# Power.net
KiCad netlist of a schematic drawn in Altium Designer
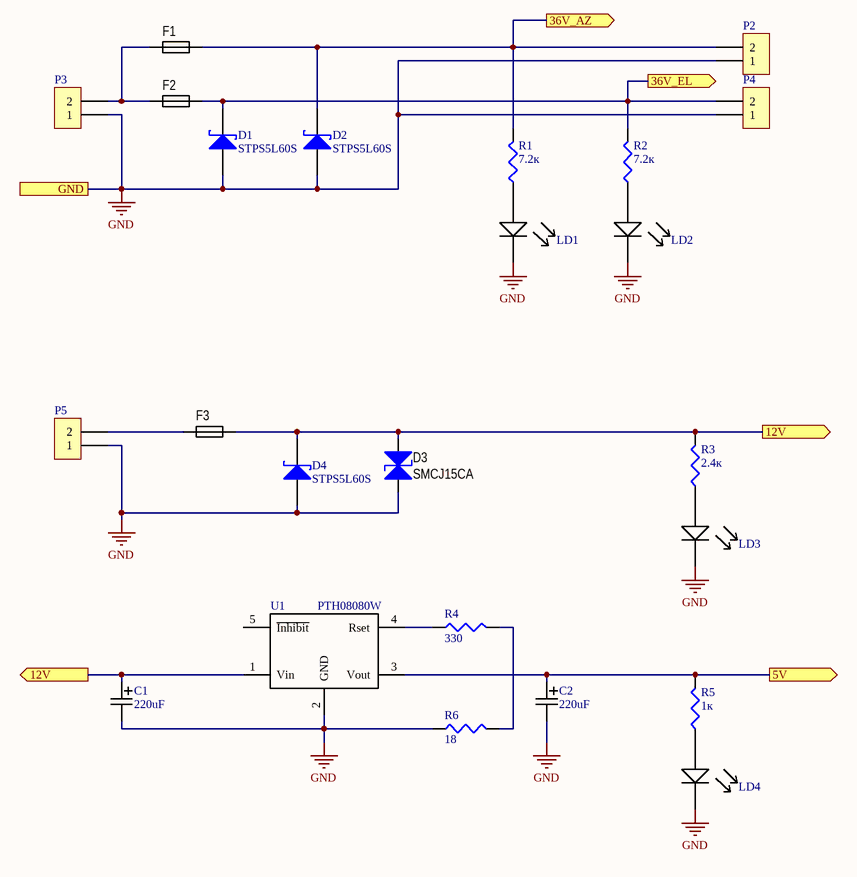
[diagram p0: Power.SchDoc]

(export (version "E")
  (design (tool "Eeschema 10.0.6"))
  (components
    (comp (ref "C1")
      (value "220uF")
      (footprint "ECAP SMD 8x10.5")
      (description "Конденсатор электролитический алюминиевый SMD 8x10.5мм")
      (libsource (lib "db") (part "ECAP SMD"))
    )
    (comp (ref "C2")
      (value "220uF")
      (footprint "ECAP SMD 8x10.5")
      (description "Конденсатор электролитический алюминиевый SMD 8x10.5мм")
      (libsource (lib "db") (part "ECAP SMD"))
    )
    (comp (ref "D1")
      (value "STPS5L60S")
      (footprint "SMCJ")
      (description "Диод Шоттки 60В 5А [SMC]")
      (libsource (lib "db") (part "STPS5L60S"))
    )
    (comp (ref "D2")
      (value "STPS5L60S")
      (footprint "SMCJ")
      (description "Диод Шоттки 60В 5А [SMC]")
      (libsource (lib "db") (part "STPS5L60S"))
    )
    (comp (ref "D3")
      (value "SMCJ15CA")
      (footprint "SMCJ_CA")
      (description "Супрессор двунаправленный")
      (libsource (lib "db") (part "SMCJ_CА"))
    )
    (comp (ref "D4")
      (value "STPS5L60S")
      (footprint "SMCJ")
      (description "Диод Шоттки 60В 5А [SMC]")
      (libsource (lib "db") (part "STPS5L60S"))
    )
    (comp (ref "F1")
      (value "FH-101C")
      (footprint "FH-101C")
      (description "Держатель предохранителя 5x20 с крышкой")
      (libsource (lib "db") (part "FH-101C"))
    )
    (comp (ref "F2")
      (value "FH-101C")
      (footprint "FH-101C")
      (description "Держатель предохранителя 5x20 с крышкой")
      (libsource (lib "db") (part "FH-101C"))
    )
    (comp (ref "F3")
      (value "FH-101C")
      (footprint "FH-101C")
      (description "Держатель предохранителя 5x20 с крышкой")
      (libsource (lib "db") (part "FH-101C"))
    )
    (comp (ref "LD1")
      (value "GNL-3012ED")
      (footprint "LED 3mm")
      (description "Светодиод красный 3мм")
      (libsource (lib "db") (part "GNL-3012ED"))
    )
    (comp (ref "LD2")
      (value "GNL-3012ED")
      (footprint "LED 3mm")
      (description "Светодиод красный 3мм")
      (libsource (lib "db") (part "GNL-3012ED"))
    )
    (comp (ref "LD3")
      (value "GNL-3012ED")
      (footprint "LED 3mm")
      (description "Светодиод красный 3мм")
      (libsource (lib "db") (part "GNL-3012ED"))
    )
    (comp (ref "LD4")
      (value "GNL-3012ED")
      (footprint "LED 3mm")
      (description "Светодиод красный 3мм")
      (libsource (lib "db") (part "GNL-3012ED"))
    )
    (comp (ref "P2")
      (value "2EDGR-5.0-02P")
      (footprint "2EDGR-5.0-02P")
      (description "Разъем штыревой на плату (папа)")
      (libsource (lib "db") (part "2EDGR-5.0-02P"))
    )
    (comp (ref "P3")
      (value "2EDGR-5.0-02P")
      (footprint "2EDGR-5.0-02P")
      (description "Разъем штыревой на плату (папа)")
      (libsource (lib "") (part "2EDGR-5.0-02P_1"))
    )
    (comp (ref "P4")
      (value "2EDGR-5.0-02P")
      (footprint "2EDGR-5.0-02P")
      (description "Разъем штыревой на плату (папа)")
      (libsource (lib "db") (part "2EDGR-5.0-02P"))
    )
    (comp (ref "P5")
      (value "15EDGRC-3.81-02")
      (footprint "15EDGRC-3.81-02")
      (description "Разъем штыревой на плату (папа)")
      (libsource (lib "db") (part "15EDGRC-3.81-02"))
    )
    (comp (ref "R1")
      (value "7.2к")
      (footprint "R1608-0603")
      (description "SMD резистор")
      (libsource (lib "db") (part "resistor"))
    )
    (comp (ref "R2")
      (value "7.2к")
      (footprint "R1608-0603")
      (description "SMD резистор")
      (libsource (lib "db") (part "resistor"))
    )
    (comp (ref "R3")
      (value "2.4к")
      (footprint "R1608-0603")
      (description "SMD резистор")
      (libsource (lib "db") (part "resistor"))
    )
    (comp (ref "R4")
      (value "330")
      (footprint "R1608-0603")
      (description "SMD резистор")
      (libsource (lib "db") (part "resistor"))
    )
    (comp (ref "R5")
      (value "1к")
      (footprint "R1608-0603")
      (description "SMD резистор")
      (libsource (lib "db") (part "resistor"))
    )
    (comp (ref "R6")
      (value "18")
      (footprint "R1608-0603")
      (description "SMD резистор")
      (libsource (lib "db") (part "resistor"))
    )
    (comp (ref "U1")
      (value "PTH08080W")
      (footprint "PTH08080W")
      (description "DC/DC преобразователь")
      (libsource (lib "db") (part "PTH08080W"))
    )
  )
  (nets
    (net (code "1") (name "/5V") (class "Default")
      (node (ref "C2") (pin "1") (pinfunction "1_1") (pintype "passive"))
      (node (ref "R5") (pin "2") (pinfunction "2_2") (pintype "passive"))
      (node (ref "U1") (pin "3") (pinfunction "Vout_3") (pintype "power_in"))
    )
    (net (code "2") (name "/12V") (class "Default")
      (node (ref "C1") (pin "1") (pinfunction "1_1") (pintype "passive"))
      (node (ref "D3") (pin "2") (pinfunction "A_2") (pintype "passive"))
      (node (ref "D4") (pin "1") (pinfunction "K_1") (pintype "passive"))
      (node (ref "F3") (pin "2") (pinfunction "2_2") (pintype "passive"))
      (node (ref "R3") (pin "2") (pinfunction "2_2") (pintype "passive"))
      (node (ref "U1") (pin "1") (pinfunction "Vin_1") (pintype "passive"))
    )
    (net (code "3") (name "/36V_AZ") (class "Default")
      (node (ref "D2") (pin "1") (pinfunction "K_1") (pintype "passive"))
      (node (ref "F1") (pin "2") (pinfunction "2_2") (pintype "passive"))
      (node (ref "P2") (pin "2") (pinfunction "2_2") (pintype "passive"))
      (node (ref "R1") (pin "2") (pinfunction "2_2") (pintype "passive"))
    )
    (net (code "4") (name "/36V_EL") (class "Default")
      (node (ref "D1") (pin "1") (pinfunction "K_1") (pintype "passive"))
      (node (ref "F2") (pin "2") (pinfunction "2_2") (pintype "passive"))
      (node (ref "P4") (pin "2") (pinfunction "2_2") (pintype "passive"))
      (node (ref "R2") (pin "2") (pinfunction "2_2") (pintype "passive"))
    )
    (net (code "5") (name "GND") (class "Default")
      (node (ref "C1") (pin "2") (pinfunction "2_2") (pintype "passive"))
      (node (ref "C2") (pin "2") (pinfunction "2_2") (pintype "passive"))
      (node (ref "D1") (pin "2") (pinfunction "A_2") (pintype "passive"))
      (node (ref "D2") (pin "2") (pinfunction "A_2") (pintype "passive"))
      (node (ref "D3") (pin "1") (pinfunction "K_1") (pintype "passive"))
      (node (ref "D4") (pin "2") (pinfunction "A_2") (pintype "passive"))
      (node (ref "LD1") (pin "1") (pinfunction "K_1") (pintype "passive"))
      (node (ref "LD2") (pin "1") (pinfunction "K_1") (pintype "passive"))
      (node (ref "LD3") (pin "1") (pinfunction "K_1") (pintype "passive"))
      (node (ref "LD4") (pin "1") (pinfunction "K_1") (pintype "passive"))
      (node (ref "P2") (pin "1") (pinfunction "1_1") (pintype "passive"))
      (node (ref "P3") (pin "1") (pinfunction "1_1") (pintype "passive"))
      (node (ref "P4") (pin "1") (pinfunction "1_1") (pintype "passive"))
      (node (ref "P5") (pin "1") (pinfunction "1_1") (pintype "passive"))
      (node (ref "R6") (pin "1") (pinfunction "1_1") (pintype "passive"))
      (node (ref "U1") (pin "2") (pinfunction "GND_2") (pintype "passive"))
    )
    (net (code "6") (name "Net-(F1-Pad1)") (class "Default")
      (node (ref "F1") (pin "1") (pinfunction "1_1") (pintype "passive"))
      (node (ref "F2") (pin "1") (pinfunction "1_1") (pintype "passive"))
      (node (ref "P3") (pin "2") (pinfunction "2_2") (pintype "passive"))
    )
    (net (code "7") (name "Net-(F3-Pad1)") (class "Default")
      (node (ref "F3") (pin "1") (pinfunction "1_1") (pintype "passive"))
      (node (ref "P5") (pin "2") (pinfunction "2_2") (pintype "passive"))
    )
    (net (code "8") (name "Net-(LD1-A)") (class "Default")
      (node (ref "LD1") (pin "2") (pinfunction "A_2") (pintype "passive"))
      (node (ref "R1") (pin "1") (pinfunction "1_1") (pintype "passive"))
    )
    (net (code "9") (name "Net-(LD2-A)") (class "Default")
      (node (ref "LD2") (pin "2") (pinfunction "A_2") (pintype "passive"))
      (node (ref "R2") (pin "1") (pinfunction "1_1") (pintype "passive"))
    )
    (net (code "10") (name "Net-(LD3-A)") (class "Default")
      (node (ref "LD3") (pin "2") (pinfunction "A_2") (pintype "passive"))
      (node (ref "R3") (pin "1") (pinfunction "1_1") (pintype "passive"))
    )
    (net (code "11") (name "Net-(LD4-A)") (class "Default")
      (node (ref "LD4") (pin "2") (pinfunction "A_2") (pintype "passive"))
      (node (ref "R5") (pin "1") (pinfunction "1_1") (pintype "passive"))
    )
    (net (code "12") (name "Net-(R4-Pad2)") (class "Default")
      (node (ref "R4") (pin "2") (pinfunction "2_2") (pintype "passive"))
      (node (ref "R6") (pin "2") (pinfunction "2_2") (pintype "passive"))
    )
    (net (code "13") (name "Net-(U1-Rset)") (class "Default")
      (node (ref "R4") (pin "1") (pinfunction "1_1") (pintype "passive"))
      (node (ref "U1") (pin "4") (pinfunction "Rset_4") (pintype "power_in"))
    )
    (net (code "14") (name "unconnected-(U1-~{Inhibit}-Pad5)") (class "Default")
      (node (ref "U1") (pin "5") (pinfunction "~{Inhibit}_5") (pintype "power_in"))
    )
  )
)
